# KMO_IO_MV2_6.net
KiCad netlist of a schematic drawn in EAGLE
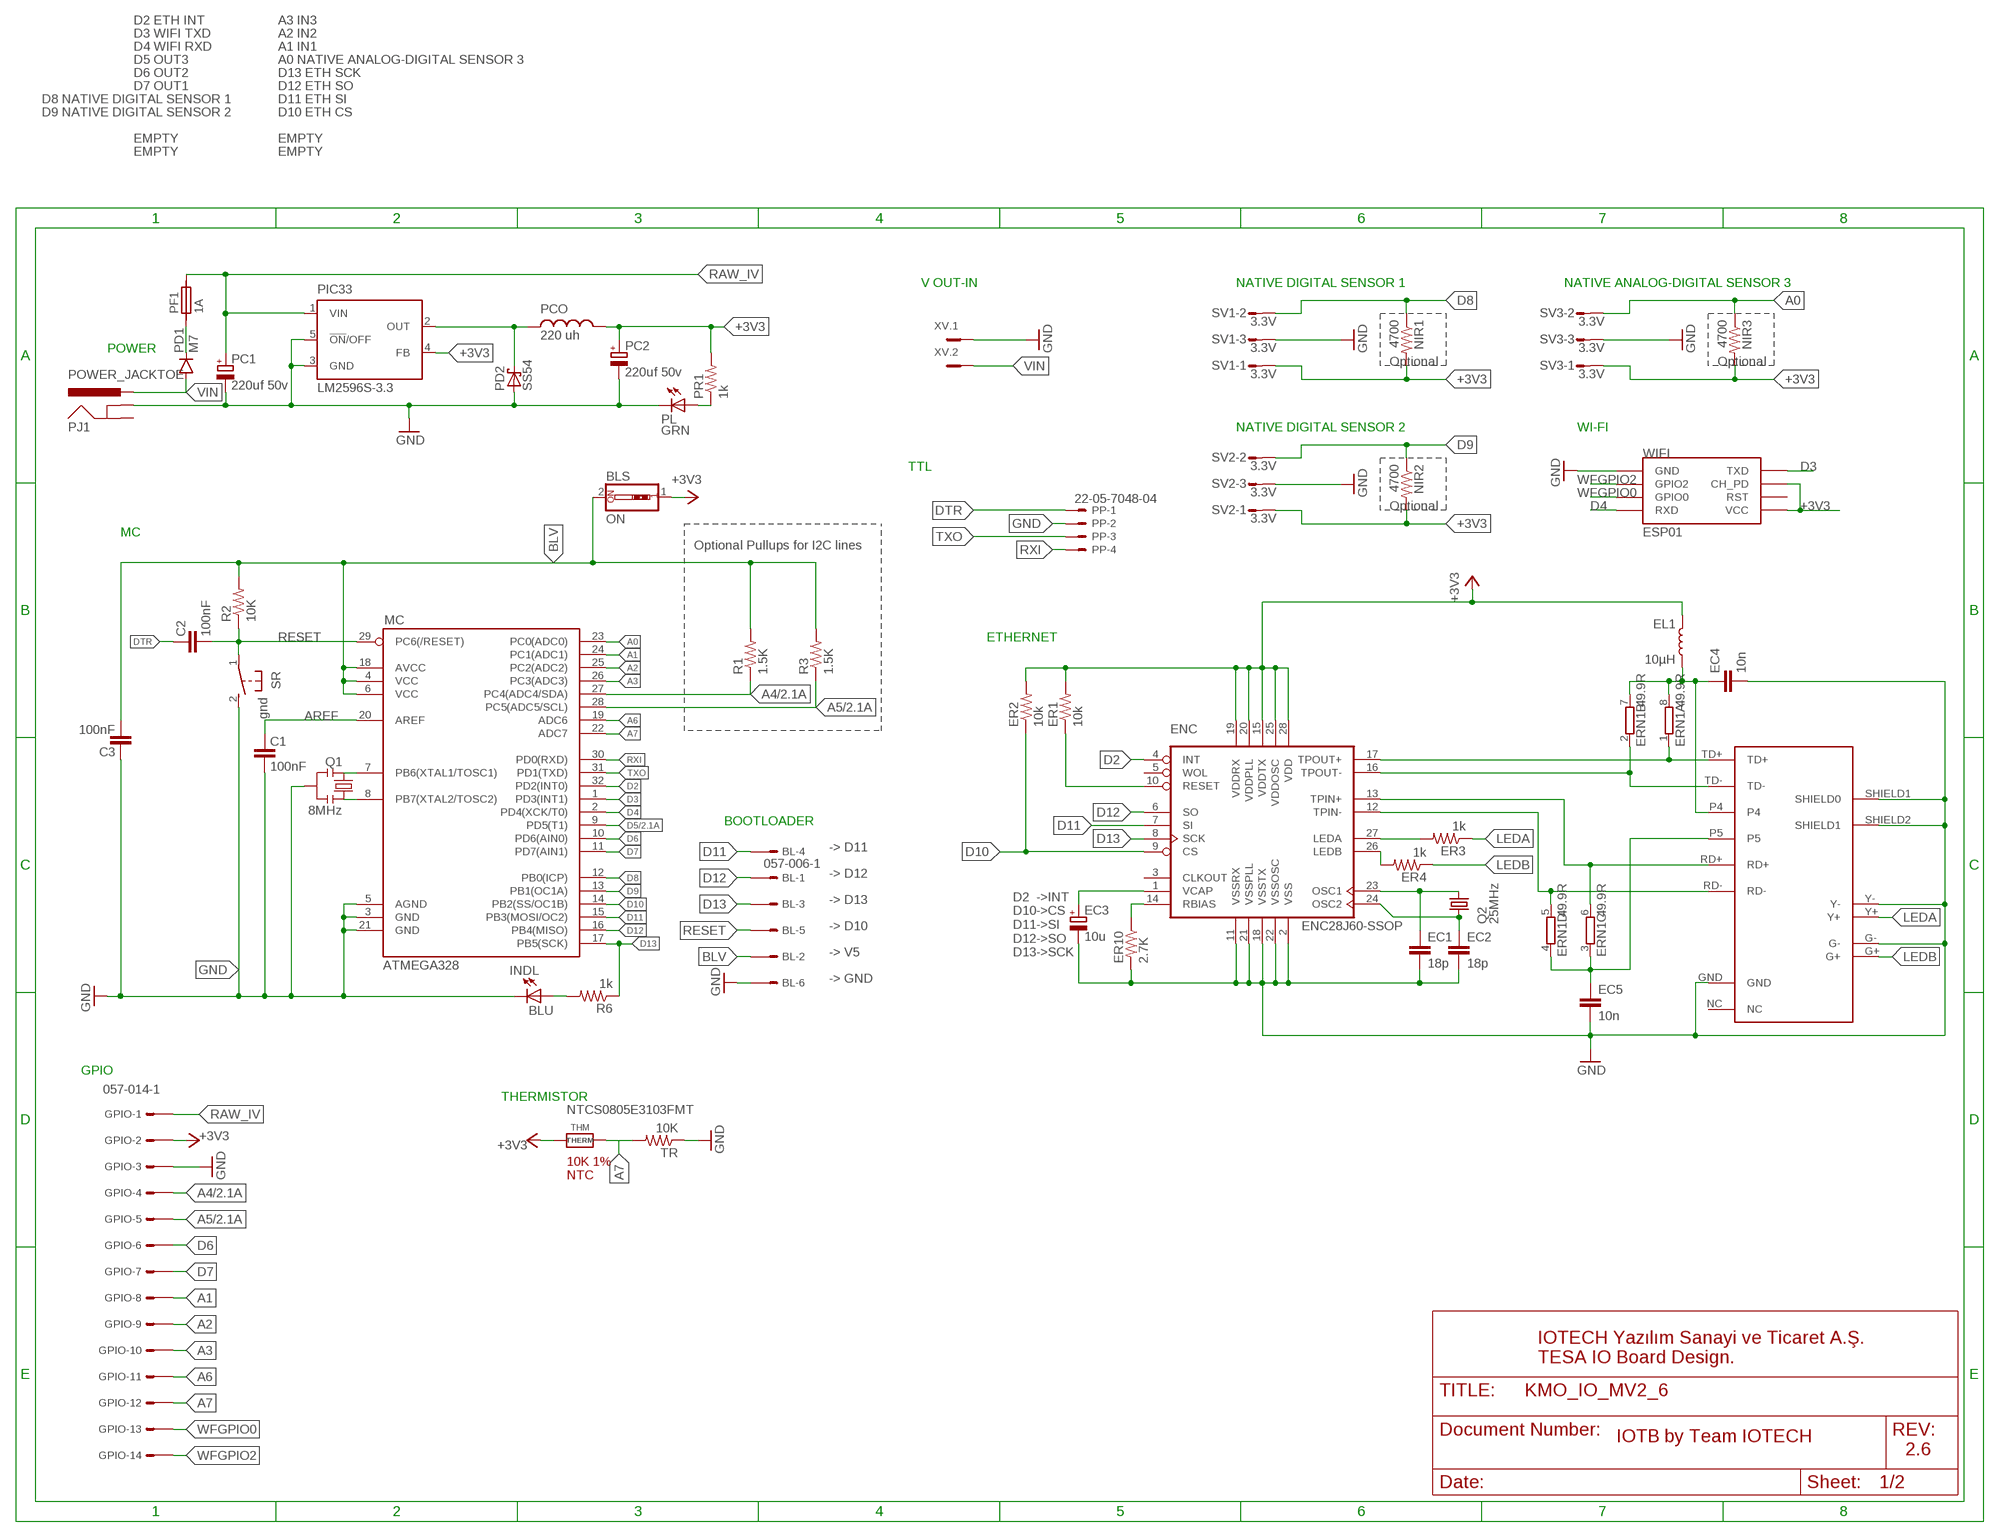
[diagram p0: schematic, sheet 1]
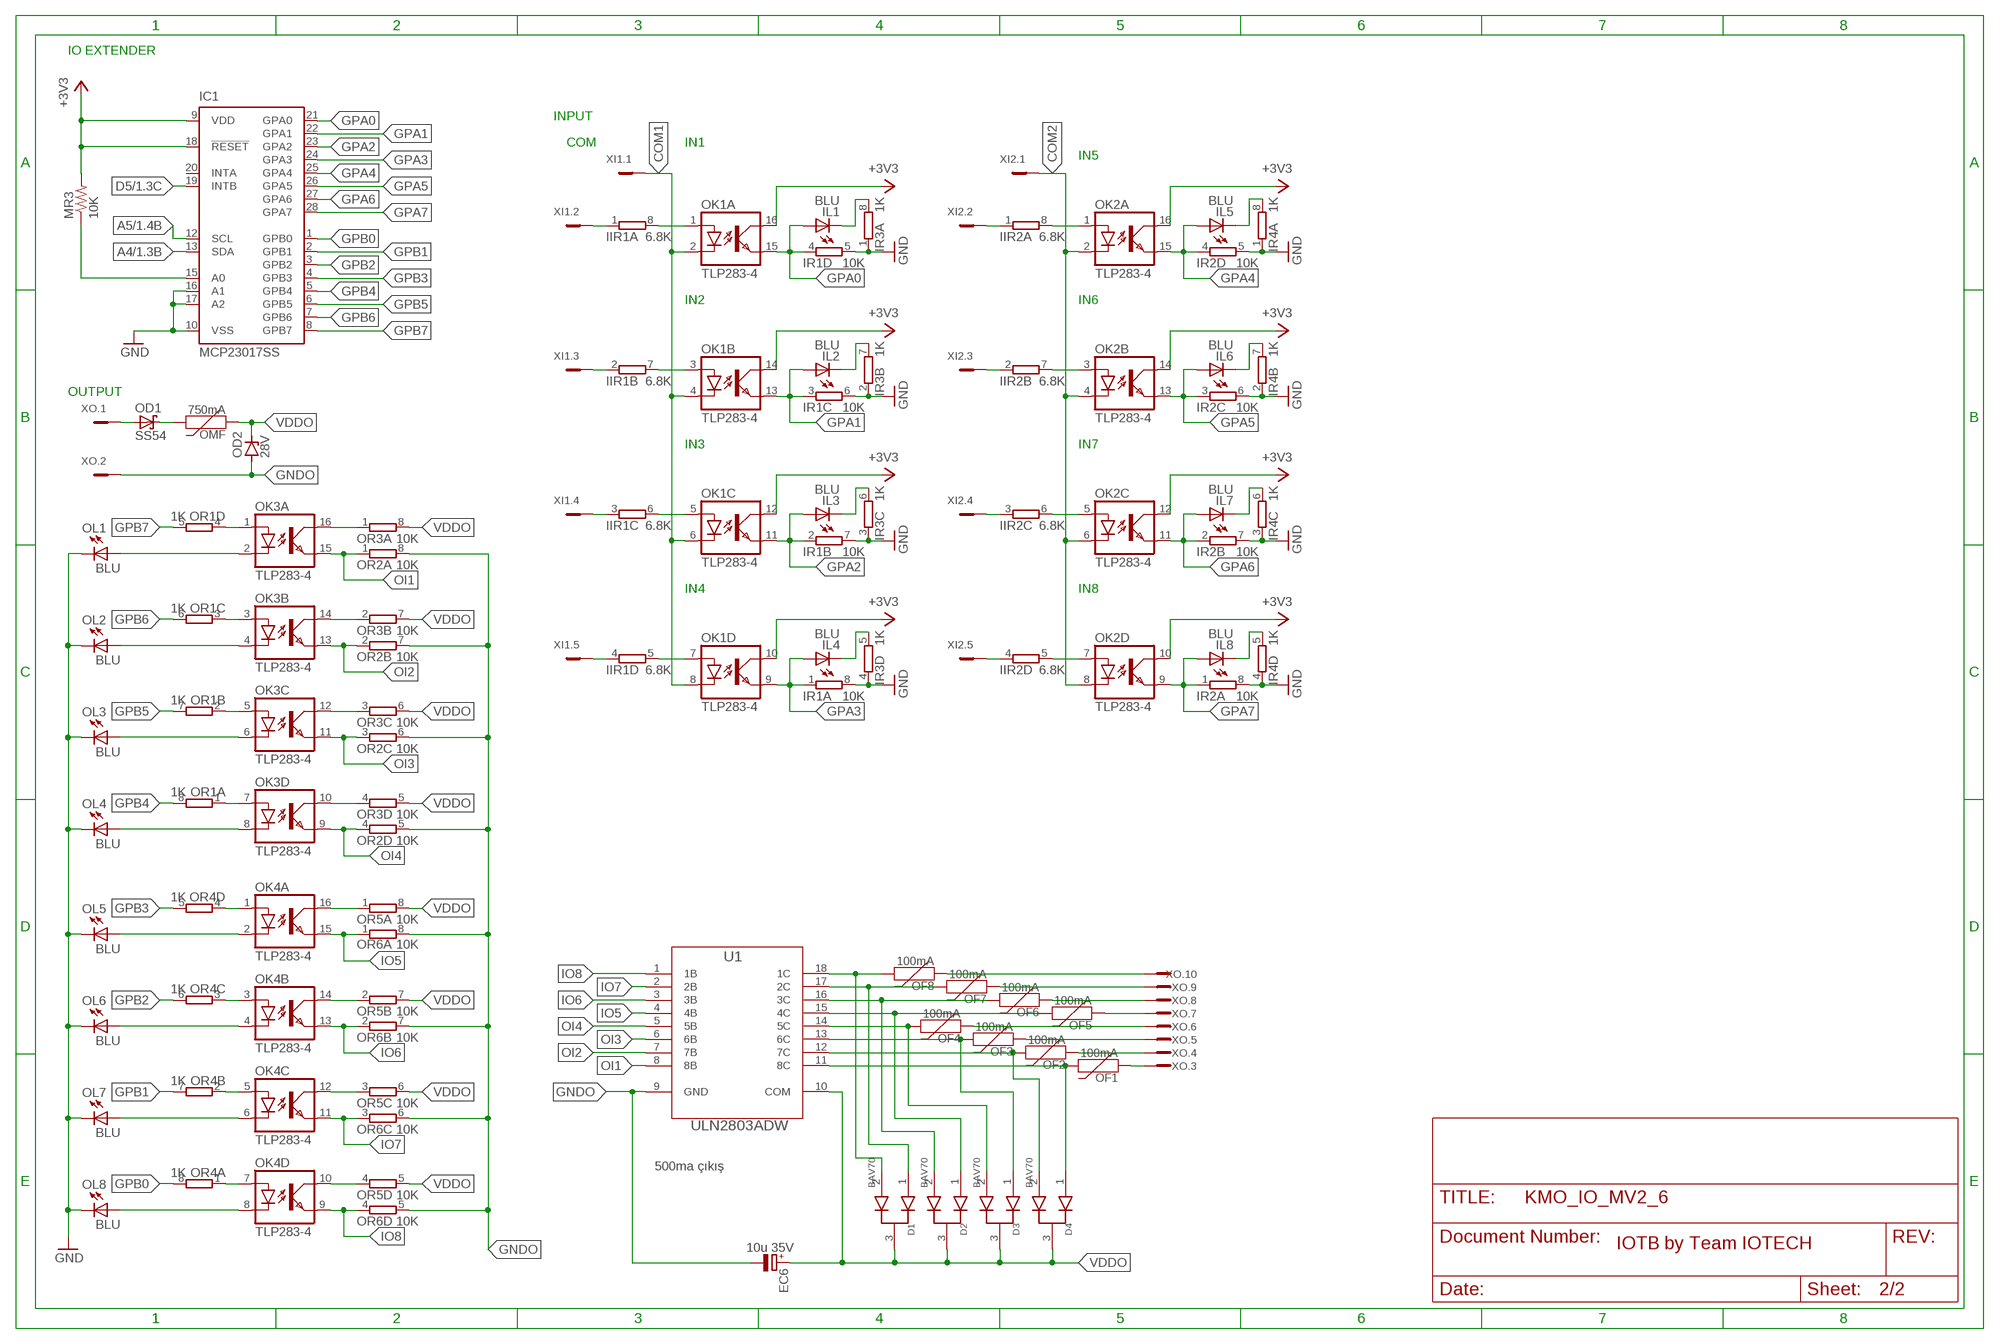
[diagram p1: schematic, sheet 2]

(export (version "E")
  (design (tool "Eeschema 10.0.6"))
  (components
    (comp (ref "D1")
      (value "BAV70")
      (footprint "eagle-import:SOT-23-3")
      (fields (field (name "MF") "Multicomp") (field (name "MP") "BAV70+"))
      (libsource (lib "eagle-import") (part "BAV70"))
    )
    (comp (ref "D2")
      (value "BAV70")
      (footprint "eagle-import:SOT-23-3")
      (fields (field (name "MF") "Multicomp") (field (name "MP") "BAV70+"))
      (libsource (lib "eagle-import") (part "BAV70"))
    )
    (comp (ref "D3")
      (value "BAV70")
      (footprint "eagle-import:SOT-23-3")
      (fields (field (name "MF") "Multicomp") (field (name "MP") "BAV70+"))
      (libsource (lib "eagle-import") (part "BAV70"))
    )
    (comp (ref "D4")
      (value "BAV70")
      (footprint "eagle-import:SOT-23-3")
      (fields (field (name "MF") "Multicomp") (field (name "MP") "BAV70+"))
      (libsource (lib "eagle-import") (part "BAV70"))
    )
    (comp (ref "EC6")
      (value "10u 35V")
      (footprint "eagle-import:CT3216")
      (libsource (lib "eagle-import") (part "CPOL-EUCT3216"))
    )
    (comp (ref "IC1")
      (value "MCP23017SS")
      (footprint "eagle-import:SSOP28")
      (fields (field (name "MF") "MICROCHIP") (field (name "MPN") "MCP23017-E/SS"))
      (libsource (lib "eagle-import") (part "MCP23017SS"))
    )
    (comp (ref "IIR1")
      (value "6.8K")
      (footprint "eagle-import:0603-ARV")
      (libsource (lib "eagle-import") (part "4R-N0603-ARV"))
    )
    (comp (ref "IIR2")
      (value "6.8K")
      (footprint "eagle-import:0603-ARV")
      (libsource (lib "eagle-import") (part "4R-N0603-ARV"))
    )
    (comp (ref "IL1")
      (value "BLU")
      (footprint "eagle-import:CHIP-LED0805")
      (libsource (lib "eagle-import") (part "LEDCHIP-LED0805"))
    )
    (comp (ref "IL2")
      (value "BLU")
      (footprint "eagle-import:CHIP-LED0805")
      (libsource (lib "eagle-import") (part "LEDCHIP-LED0805"))
    )
    (comp (ref "IL3")
      (value "BLU")
      (footprint "eagle-import:CHIP-LED0805")
      (libsource (lib "eagle-import") (part "LEDCHIP-LED0805"))
    )
    (comp (ref "IL4")
      (value "BLU")
      (footprint "eagle-import:CHIP-LED0805")
      (libsource (lib "eagle-import") (part "LEDCHIP-LED0805"))
    )
    (comp (ref "IL5")
      (value "BLU")
      (footprint "eagle-import:CHIP-LED0805")
      (libsource (lib "eagle-import") (part "LEDCHIP-LED0805"))
    )
    (comp (ref "IL6")
      (value "BLU")
      (footprint "eagle-import:CHIP-LED0805")
      (libsource (lib "eagle-import") (part "LEDCHIP-LED0805"))
    )
    (comp (ref "IL7")
      (value "BLU")
      (footprint "eagle-import:CHIP-LED0805")
      (libsource (lib "eagle-import") (part "LEDCHIP-LED0805"))
    )
    (comp (ref "IL8")
      (value "BLU")
      (footprint "eagle-import:CHIP-LED0805")
      (libsource (lib "eagle-import") (part "LEDCHIP-LED0805"))
    )
    (comp (ref "IR1")
      (value "10K")
      (footprint "eagle-import:0603-ARV")
      (libsource (lib "eagle-import") (part "4R-N0603-ARV"))
    )
    (comp (ref "IR2")
      (value "10K")
      (footprint "eagle-import:0603-ARV")
      (libsource (lib "eagle-import") (part "4R-N0603-ARV"))
    )
    (comp (ref "IR3")
      (value "1K")
      (footprint "eagle-import:0603-ARV")
      (libsource (lib "eagle-import") (part "4R-N0603-ARV"))
    )
    (comp (ref "IR4")
      (value "1K")
      (footprint "eagle-import:0603-ARV")
      (libsource (lib "eagle-import") (part "4R-N0603-ARV"))
    )
    (comp (ref "MR3")
      (value "10K")
      (footprint "eagle-import:0805")
      (libsource (lib "eagle-import") (part "RESISTOR0805-RES"))
    )
    (comp (ref "OD1")
      (value "SS54")
      (footprint "eagle-import:SMB")
      (libsource (lib "eagle-import") (part "SCHOTTKY-DIODESMD"))
    )
    (comp (ref "OD2")
      (value "28V")
      (footprint "eagle-import:SMB")
      (libsource (lib "eagle-import") (part "ZENER-DIODESMB"))
    )
    (comp (ref "OF1")
      (value "100mA")
      (footprint "eagle-import:1206")
      (libsource (lib "eagle-import") (part "PPTC_0.75A"))
    )
    (comp (ref "OF2")
      (value "100mA")
      (footprint "eagle-import:1206")
      (libsource (lib "eagle-import") (part "PPTC_0.75A"))
    )
    (comp (ref "OF3")
      (value "100mA")
      (footprint "eagle-import:1206")
      (libsource (lib "eagle-import") (part "PPTC_0.75A"))
    )
    (comp (ref "OF4")
      (value "100mA")
      (footprint "eagle-import:1206")
      (libsource (lib "eagle-import") (part "PPTC_0.75A"))
    )
    (comp (ref "OF5")
      (value "100mA")
      (footprint "eagle-import:1206")
      (libsource (lib "eagle-import") (part "PPTC_0.75A"))
    )
    (comp (ref "OF6")
      (value "100mA")
      (footprint "eagle-import:1206")
      (libsource (lib "eagle-import") (part "PPTC_0.75A"))
    )
    (comp (ref "OF7")
      (value "100mA")
      (footprint "eagle-import:1206")
      (libsource (lib "eagle-import") (part "PPTC_0.75A"))
    )
    (comp (ref "OF8")
      (value "100mA")
      (footprint "eagle-import:1206")
      (libsource (lib "eagle-import") (part "PPTC_0.75A"))
    )
    (comp (ref "OK1")
      (value "TLP283-4")
      (footprint "eagle-import:MINI-FLAT-16")
      (fields (field (name "SPICEPREFIX") "O"))
      (libsource (lib "eagle-import") (part "TLP283-4"))
    )
    (comp (ref "OK2")
      (value "TLP283-4")
      (footprint "eagle-import:MINI-FLAT-16")
      (fields (field (name "SPICEPREFIX") "O"))
      (libsource (lib "eagle-import") (part "TLP283-4"))
    )
    (comp (ref "OK3")
      (value "TLP283-4")
      (footprint "eagle-import:MINI-FLAT-16")
      (libsource (lib "eagle-import") (part "TLP283-4"))
    )
    (comp (ref "OK4")
      (value "TLP283-4")
      (footprint "eagle-import:MINI-FLAT-16")
      (libsource (lib "eagle-import") (part "TLP283-4"))
    )
    (comp (ref "OL1")
      (value "BLU")
      (footprint "eagle-import:CHIP-LED0805")
      (libsource (lib "eagle-import") (part "LEDCHIP-LED0805"))
    )
    (comp (ref "OL2")
      (value "BLU")
      (footprint "eagle-import:CHIP-LED0805")
      (libsource (lib "eagle-import") (part "LEDCHIP-LED0805"))
    )
    (comp (ref "OL3")
      (value "BLU")
      (footprint "eagle-import:CHIP-LED0805")
      (libsource (lib "eagle-import") (part "LEDCHIP-LED0805"))
    )
    (comp (ref "OL4")
      (value "BLU")
      (footprint "eagle-import:CHIP-LED0805")
      (libsource (lib "eagle-import") (part "LEDCHIP-LED0805"))
    )
    (comp (ref "OL5")
      (value "BLU")
      (footprint "eagle-import:CHIP-LED0805")
      (libsource (lib "eagle-import") (part "LEDCHIP-LED0805"))
    )
    (comp (ref "OL6")
      (value "BLU")
      (footprint "eagle-import:CHIP-LED0805")
      (libsource (lib "eagle-import") (part "LEDCHIP-LED0805"))
    )
    (comp (ref "OL7")
      (value "BLU")
      (footprint "eagle-import:CHIP-LED0805")
      (libsource (lib "eagle-import") (part "LEDCHIP-LED0805"))
    )
    (comp (ref "OL8")
      (value "BLU")
      (footprint "eagle-import:CHIP-LED0805")
      (libsource (lib "eagle-import") (part "LEDCHIP-LED0805"))
    )
    (comp (ref "OMF")
      (value "750mA")
      (footprint "eagle-import:1206")
      (libsource (lib "eagle-import") (part "PPTC_0.75A"))
    )
    (comp (ref "OR1")
      (value "1K")
      (footprint "eagle-import:0603-ARV")
      (libsource (lib "eagle-import") (part "4R-N0603-ARV"))
    )
    (comp (ref "OR2")
      (value "10K")
      (footprint "eagle-import:0603-ARV")
      (libsource (lib "eagle-import") (part "4R-N0603-ARV"))
    )
    (comp (ref "OR3")
      (value "10K")
      (footprint "eagle-import:0603-ARV")
      (libsource (lib "eagle-import") (part "4R-N0603-ARV"))
    )
    (comp (ref "OR4")
      (value "1K")
      (footprint "eagle-import:0603-ARV")
      (libsource (lib "eagle-import") (part "4R-N0603-ARV"))
    )
    (comp (ref "OR5")
      (value "10K")
      (footprint "eagle-import:0603-ARV")
      (libsource (lib "eagle-import") (part "4R-N0603-ARV"))
    )
    (comp (ref "OR6")
      (value "10K")
      (footprint "eagle-import:0603-ARV")
      (libsource (lib "eagle-import") (part "4R-N0603-ARV"))
    )
    (comp (ref "U1")
      (value "ULN2803ADW")
      (footprint "eagle-import:SOIC127P1030X265-18N")
      (libsource (lib "eagle-import") (part "ULN2803ADW"))
    )
    (comp (ref "XI1")
      (value "MC5")
      (footprint "eagle-import:MC5")
      (libsource (lib "eagle-import") (part "MC5"))
    )
    (comp (ref "XI2")
      (value "MC5")
      (footprint "eagle-import:MC5")
      (libsource (lib "eagle-import") (part "MC5"))
    )
    (comp (ref "XO")
      (value "MC10")
      (footprint "eagle-import:MC10")
      (libsource (lib "eagle-import") (part "MC10"))
    )
    (comp (ref "BL")
      (value "057-006-1")
      (footprint "eagle-import:057-006-1")
      (libsource (lib "eagle-import") (part "057-006-1"))
    )
    (comp (ref "BLS")
      (value "ON")
      (footprint "eagle-import:EDG-01")
      (libsource (lib "eagle-import") (part "SW_DIP-1"))
    )
    (comp (ref "C1")
      (value "100nF")
      (footprint "eagle-import:0805")
      (libsource (lib "eagle-import") (part "CAP0805"))
    )
    (comp (ref "C2")
      (value "100nF")
      (footprint "eagle-import:0805")
      (libsource (lib "eagle-import") (part "CAP0805"))
    )
    (comp (ref "C3")
      (value "100nF")
      (footprint "eagle-import:0805")
      (libsource (lib "eagle-import") (part "CAP0805"))
    )
    (comp (ref "EC1")
      (value "18p")
      (footprint "eagle-import:0805")
      (libsource (lib "eagle-import") (part "CAP0805"))
    )
    (comp (ref "EC2")
      (value "18p")
      (footprint "eagle-import:0805")
      (libsource (lib "eagle-import") (part "CAP0805"))
    )
    (comp (ref "EC3")
      (value "10u")
      (footprint "eagle-import:CT3216")
      (libsource (lib "eagle-import") (part "CPOL-EUCT3216"))
    )
    (comp (ref "EC4")
      (value "10n")
      (footprint "eagle-import:0805")
      (libsource (lib "eagle-import") (part "CAP0805"))
    )
    (comp (ref "EC5")
      (value "10n")
      (footprint "eagle-import:0805")
      (libsource (lib "eagle-import") (part "CAP0805"))
    )
    (comp (ref "EL1")
      (value "10µH")
      (footprint "eagle-import:0805")
      (libsource (lib "eagle-import") (part "INDUCTOR-0805-3.3UH"))
    )
    (comp (ref "ENC")
      (value "ENC28J60-SSOP")
      (footprint "eagle-import:SSOP28")
      (libsource (lib "eagle-import") (part "ENC28J60-SSOP"))
    )
    (comp (ref "ER1")
      (value "10k")
      (footprint "eagle-import:0805")
      (libsource (lib "eagle-import") (part "RESISTOR0805-RES"))
    )
    (comp (ref "ER2")
      (value "10k")
      (footprint "eagle-import:0805")
      (libsource (lib "eagle-import") (part "RESISTOR0805-RES"))
    )
    (comp (ref "ER3")
      (value "1k")
      (footprint "eagle-import:0805")
      (libsource (lib "eagle-import") (part "RESISTOR0805-RES"))
    )
    (comp (ref "ER4")
      (value "1k")
      (footprint "eagle-import:0805")
      (libsource (lib "eagle-import") (part "RESISTOR0805-RES"))
    )
    (comp (ref "ER10")
      (value "2.7K")
      (footprint "eagle-import:0805")
      (libsource (lib "eagle-import") (part "RESISTOR0805-RES"))
    )
    (comp (ref "ERN1")
      (value "49.9R")
      (footprint "eagle-import:0603-ARV")
      (libsource (lib "eagle-import") (part "4R-N0603-ARV"))
    )
    (comp (ref "GPIO")
      (value "057-014-1")
      (footprint "eagle-import:057-014-1")
      (libsource (lib "eagle-import") (part "057-014-1"))
    )
    (comp (ref "INDL")
      (value "BLU")
      (footprint "eagle-import:CHIP-LED0805")
      (libsource (lib "eagle-import") (part "LEDCHIP-LED0805"))
    )
    (comp (ref "MC")
      (value "ATMEGA328")
      (footprint "eagle-import:TQFP32-08")
      (libsource (lib "eagle-import") (part "ATMEGA168"))
    )
    (comp (ref "NIR1")
      (value "4700")
      (footprint "eagle-import:0805")
      (libsource (lib "eagle-import") (part "RESISTOR0805-RES"))
    )
    (comp (ref "NIR2")
      (value "4700")
      (footprint "eagle-import:0805")
      (libsource (lib "eagle-import") (part "RESISTOR0805-RES"))
    )
    (comp (ref "NIR3")
      (value "4700")
      (footprint "eagle-import:0805")
      (libsource (lib "eagle-import") (part "RESISTOR0805-RES"))
    )
    (comp (ref "PC1")
      (value "220uf 50v")
      (footprint "eagle-import:140CLH-1010")
      (libsource (lib "eagle-import") (part "CPOL-EU140CLH-1010"))
    )
    (comp (ref "PC2")
      (value "220uf 50v")
      (footprint "eagle-import:140CLH-1010")
      (libsource (lib "eagle-import") (part "CPOL-EU140CLH-1010"))
    )
    (comp (ref "PCO")
      (value "220 uh")
      (footprint "eagle-import:MSS1260")
      (libsource (lib "eagle-import") (part "MSS1260"))
    )
    (comp (ref "PD1")
      (value "M7")
      (footprint "eagle-import:SMA-DIODE")
      (libsource (lib "eagle-import") (part "DIODESMA"))
    )
    (comp (ref "PD2")
      (value "SS54")
      (footprint "eagle-import:SMB")
      (libsource (lib "eagle-import") (part "SCHOTTKY-DIODESMD"))
    )
    (comp (ref "PF1")
      (value "1A")
      (footprint "eagle-import:1820")
      (libsource (lib "eagle-import") (part "SIBA194600"))
    )
    (comp (ref "PIC33")
      (value "LM2596S-3.3")
      (footprint "eagle-import:TO263-5")
      (fields
        (field (name "MF") "NATIONAL SEMICONDUCTOR")
        (field (name "MPN") "LM2596S-ADJ/NOPB")
        (field (name "SPICEPREFIX") "X")
      )
      (libsource (lib "eagle-import") (part "LM2596S"))
    )
    (comp (ref "PJ1")
      (value "POWER_JACKTOE")
      (footprint "eagle-import:POWER_JACK_SMD_OVERPASTE_TOE")
      (libsource (lib "eagle-import") (part "POWER_JACKTOE"))
    )
    (comp (ref "PL")
      (value "GRN")
      (footprint "eagle-import:CHIP-LED0805")
      (libsource (lib "eagle-import") (part "LEDCHIP-LED0805"))
    )
    (comp (ref "PP")
      (value "22-05-7048-04")
      (footprint "eagle-import:7395-04")
      (fields (field (name "MF") "MOLEX"))
      (libsource (lib "eagle-import") (part "22-?-0405-7048"))
    )
    (comp (ref "PR1")
      (value "1k")
      (footprint "eagle-import:0805")
      (libsource (lib "eagle-import") (part "RESISTOR0805-RES"))
    )
    (comp (ref "Q1")
      (value "8MHz")
      (footprint "eagle-import:RESONATOR-SMD-1_1")
      (libsource (lib "eagle-import") (part "RESONATOR1{colon}1"))
    )
    (comp (ref "Q2")
      (value "25MHz")
      (footprint "eagle-import:5.0X3.2_2")
      (libsource (lib "eagle-import") (part "KX-9B"))
    )
    (comp (ref "R1")
      (value "1.5K")
      (footprint "eagle-import:0805")
      (libsource (lib "eagle-import") (part "RESISTOR0805-RES"))
    )
    (comp (ref "R2")
      (value "10K")
      (footprint "eagle-import:0805")
      (libsource (lib "eagle-import") (part "RESISTOR0805-RES"))
    )
    (comp (ref "R3")
      (value "1.5K")
      (footprint "eagle-import:0805")
      (libsource (lib "eagle-import") (part "RESISTOR0805-RES"))
    )
    (comp (ref "R6")
      (value "1k")
      (footprint "eagle-import:0805")
      (libsource (lib "eagle-import") (part "RESISTOR0805-RES"))
    )
    (comp (ref "SR")
      (value "gnd")
      (footprint "eagle-import:B3F-31XX")
      (fields (field (name "MPN") "B3F-3100"))
      (libsource (lib "eagle-import") (part "31-XX"))
    )
    (comp (ref "SV1")
      (value "3.3V")
      (footprint "eagle-import:S03P")
      (libsource (lib "eagle-import") (part "S03P"))
    )
    (comp (ref "SV2")
      (value "3.3V")
      (footprint "eagle-import:S03P")
      (libsource (lib "eagle-import") (part "S03P"))
    )
    (comp (ref "SV3")
      (value "3.3V")
      (footprint "eagle-import:S03P")
      (libsource (lib "eagle-import") (part "S03P"))
    )
    (comp (ref "THM")
      (value "THERM")
      (footprint "eagle-import:MICROBUILDER_0805_NOTHERMALS")
      (libsource (lib "eagle-import") (part "MICROBUILDER_RESISTOR0805_NOTHERMALS"))
    )
    (comp (ref "TR")
      (value "10K")
      (footprint "eagle-import:0805")
      (libsource (lib "eagle-import") (part "RESISTOR0805-RES"))
    )
    (comp (ref "U$2")
      (value "HR911105A")
      (footprint "eagle-import:RJ45")
      (libsource (lib "eagle-import") (part "HR911105A"))
    )
    (comp (ref "WIFI")
      (value "ESP01")
      (footprint "eagle-import:ESP01")
      (libsource (lib "eagle-import") (part "ESP01"))
    )
    (comp (ref "XV")
      (value "MC2")
      (footprint "eagle-import:MC2")
      (libsource (lib "eagle-import") (part "MC2"))
    )
  )
  (nets
    (net (code "1") (name "+3V3") (class "Default")
      (node (ref "BLS") (pin "1") (pinfunction "1_1") (pintype "passive"))
      (node (ref "EL1") (pin "1") (pinfunction "1_1") (pintype "passive"))
      (node (ref "ENC") (pin "15") (pinfunction "VDDTX_15") (pintype "power_in"))
      (node (ref "ENC") (pin "19") (pinfunction "VDDRX_19") (pintype "power_in"))
      (node (ref "ENC") (pin "20") (pinfunction "VDDPLL_20") (pintype "power_in"))
      (node (ref "ENC") (pin "25") (pinfunction "VDDOSC_25") (pintype "power_in"))
      (node (ref "ENC") (pin "28") (pinfunction "VDD_28") (pintype "power_in"))
      (node (ref "ER1") (pin "2") (pinfunction "2_2") (pintype "passive"))
      (node (ref "ER2") (pin "2") (pinfunction "2_2") (pintype "passive"))
      (node (ref "GPIO") (pin "2") (pinfunction "S_2") (pintype "passive"))
      (node (ref "IC1") (pin "18") (pinfunction "~{RESET}_18") (pintype "input"))
      (node (ref "IC1") (pin "9") (pinfunction "VDD_9") (pintype "power_in"))
      (node (ref "MR3") (pin "2") (pinfunction "2_2") (pintype "passive"))
      (node (ref "NIR1") (pin "2") (pinfunction "2_2") (pintype "passive"))
      (node (ref "NIR2") (pin "2") (pinfunction "2_2") (pintype "passive"))
      (node (ref "NIR3") (pin "2") (pinfunction "2_2") (pintype "passive"))
      (node (ref "OK1") (pin "10") (pinfunction "COL_10") (pintype "passive"))
      (node (ref "OK1") (pin "12") (pinfunction "COL_12") (pintype "passive"))
      (node (ref "OK1") (pin "14") (pinfunction "COL_14") (pintype "passive"))
      (node (ref "OK1") (pin "16") (pinfunction "COL_16") (pintype "passive"))
      (node (ref "OK2") (pin "10") (pinfunction "COL_10") (pintype "passive"))
      (node (ref "OK2") (pin "12") (pinfunction "COL_12") (pintype "passive"))
      (node (ref "OK2") (pin "14") (pinfunction "COL_14") (pintype "passive"))
      (node (ref "OK2") (pin "16") (pinfunction "COL_16") (pintype "passive"))
      (node (ref "PC2") (pin "+") (pinfunction "+_+") (pintype "passive"))
      (node (ref "PCO") (pin "P$1") (pinfunction "P$1_P$1") (pintype "passive"))
      (node (ref "PIC33") (pin "4") (pinfunction "FB_4") (pintype "input"))
      (node (ref "PR1") (pin "2") (pinfunction "2_2") (pintype "passive"))
      (node (ref "SV1") (pin "1") (pinfunction "S_1") (pintype "passive"))
      (node (ref "SV2") (pin "1") (pinfunction "S_1") (pintype "passive"))
      (node (ref "SV3") (pin "1") (pinfunction "S_1") (pintype "passive"))
      (node (ref "THM") (pin "1") (pinfunction "1_1") (pintype "passive"))
      (node (ref "WIFI") (pin "CH_PD") (pinfunction "CH_PD_CH_PD") (pintype "bidirectional"))
      (node (ref "WIFI") (pin "VCC") (pinfunction "VCC_VCC") (pintype "bidirectional"))
    )
    (net (code "2") (name "A0") (class "Default")
      (node (ref "MC") (pin "23") (pinfunction "PC0(ADC0)_23") (pintype "bidirectional"))
      (node (ref "NIR3") (pin "1") (pinfunction "1_1") (pintype "passive"))
      (node (ref "SV3") (pin "2") (pinfunction "S_2") (pintype "passive"))
    )
    (net (code "3") (name "A1") (class "Default")
      (node (ref "GPIO") (pin "8") (pinfunction "S_8") (pintype "passive"))
      (node (ref "MC") (pin "24") (pinfunction "PC1(ADC1)_24") (pintype "bidirectional"))
    )
    (net (code "4") (name "A2") (class "Default")
      (node (ref "GPIO") (pin "9") (pinfunction "S_9") (pintype "passive"))
      (node (ref "MC") (pin "25") (pinfunction "PC2(ADC2)_25") (pintype "bidirectional"))
    )
    (net (code "5") (name "A3") (class "Default")
      (node (ref "GPIO") (pin "10") (pinfunction "S_10") (pintype "passive"))
      (node (ref "MC") (pin "26") (pinfunction "PC3(ADC3)_26") (pintype "bidirectional"))
    )
    (net (code "6") (name "A4") (class "Default")
      (node (ref "GPIO") (pin "4") (pinfunction "S_4") (pintype "passive"))
      (node (ref "IC1") (pin "13") (pinfunction "SDA_13") (pintype "bidirectional"))
      (node (ref "MC") (pin "27") (pinfunction "PC4(ADC4/SDA)_27") (pintype "bidirectional"))
      (node (ref "R1") (pin "1") (pinfunction "1_1") (pintype "passive"))
    )
    (net (code "7") (name "A5") (class "Default")
      (node (ref "GPIO") (pin "5") (pinfunction "S_5") (pintype "passive"))
      (node (ref "IC1") (pin "12") (pinfunction "SCL_12") (pintype "input"))
      (node (ref "MC") (pin "28") (pinfunction "PC5(ADC5/SCL)_28") (pintype "bidirectional"))
      (node (ref "R3") (pin "1") (pinfunction "1_1") (pintype "passive"))
    )
    (net (code "8") (name "A6") (class "Default")
      (node (ref "GPIO") (pin "11") (pinfunction "S_11") (pintype "passive"))
      (node (ref "MC") (pin "19") (pinfunction "ADC6_19") (pintype "bidirectional"))
    )
    (net (code "9") (name "A7") (class "Default")
      (node (ref "GPIO") (pin "12") (pinfunction "S_12") (pintype "passive"))
      (node (ref "MC") (pin "22") (pinfunction "ADC7_22") (pintype "bidirectional"))
      (node (ref "THM") (pin "2") (pinfunction "2_2") (pintype "passive"))
      (node (ref "TR") (pin "2") (pinfunction "2_2") (pintype "passive"))
    )
    (net (code "10") (name "AREF") (class "Default")
      (node (ref "C1") (pin "2") (pinfunction "2_2") (pintype "passive"))
      (node (ref "MC") (pin "20") (pinfunction "AREF_20") (pintype "bidirectional"))
    )
    (net (code "11") (name "BLV") (class "Default")
      (node (ref "BL") (pin "2") (pinfunction "S_2") (pintype "passive"))
      (node (ref "BLS") (pin "2") (pinfunction "2_2") (pintype "passive"))
      (node (ref "C3") (pin "1") (pinfunction "1_1") (pintype "passive"))
      (node (ref "MC") (pin "18") (pinfunction "AVCC_18") (pintype "bidirectional"))
      (node (ref "MC") (pin "4") (pinfunction "VCC_4") (pintype "bidirectional"))
      (node (ref "MC") (pin "6") (pinfunction "VCC_6") (pintype "bidirectional"))
      (node (ref "R1") (pin "2") (pinfunction "2_2") (pintype "passive"))
      (node (ref "R2") (pin "2") (pinfunction "2_2") (pintype "passive"))
      (node (ref "R3") (pin "2") (pinfunction "2_2") (pintype "passive"))
    )
    (net (code "12") (name "COM1") (class "Default")
      (node (ref "OK1") (pin "2") (pinfunction "C_2") (pintype "passive"))
      (node (ref "OK1") (pin "4") (pinfunction "C_4") (pintype "passive"))
      (node (ref "OK1") (pin "6") (pinfunction "C_6") (pintype "passive"))
      (node (ref "OK1") (pin "8") (pinfunction "C_8") (pintype "passive"))
      (node (ref "XI1") (pin "1") (pinfunction "SK_1") (pintype "passive"))
    )
    (net (code "13") (name "COM2") (class "Default")
      (node (ref "OK2") (pin "2") (pinfunction "C_2") (pintype "passive"))
      (node (ref "OK2") (pin "4") (pinfunction "C_4") (pintype "passive"))
      (node (ref "OK2") (pin "6") (pinfunction "C_6") (pintype "passive"))
      (node (ref "OK2") (pin "8") (pinfunction "C_8") (pintype "passive"))
      (node (ref "XI2") (pin "1") (pinfunction "SK_1") (pintype "passive"))
    )
    (net (code "14") (name "D2") (class "Default")
      (node (ref "ENC") (pin "4") (pinfunction "INT_4") (pintype "output"))
      (node (ref "MC") (pin "32") (pinfunction "PD2(INT0)_32") (pintype "bidirectional"))
    )
    (net (code "15") (name "D3") (class "Default")
      (node (ref "MC") (pin "1") (pinfunction "PD3(INT1)_1") (pintype "bidirectional"))
      (node (ref "WIFI") (pin "TX") (pinfunction "TXD_TX") (pintype "bidirectional"))
    )
    (net (code "16") (name "D4") (class "Default")
      (node (ref "MC") (pin "2") (pinfunction "PD4(XCK/T0)_2") (pintype "bidirectional"))
      (node (ref "WIFI") (pin "RX") (pinfunction "RXD_RX") (pintype "bidirectional"))
    )
    (net (code "17") (name "D5") (class "Default")
      (node (ref "IC1") (pin "19") (pinfunction "INTB_19") (pintype "output"))
      (node (ref "MC") (pin "9") (pinfunction "PD5(T1)_9") (pintype "bidirectional"))
    )
    (net (code "18") (name "D6") (class "Default")
      (node (ref "GPIO") (pin "6") (pinfunction "S_6") (pintype "passive"))
      (node (ref "MC") (pin "10") (pinfunction "PD6(AIN0)_10") (pintype "bidirectional"))
    )
    (net (code "19") (name "D7") (class "Default")
      (node (ref "GPIO") (pin "7") (pinfunction "S_7") (pintype "passive"))
      (node (ref "MC") (pin "11") (pinfunction "PD7(AIN1)_11") (pintype "bidirectional"))
    )
    (net (code "20") (name "D8") (class "Default")
      (node (ref "MC") (pin "12") (pinfunction "PB0(ICP)_12") (pintype "bidirectional"))
      (node (ref "NIR1") (pin "1") (pinfunction "1_1") (pintype "passive"))
      (node (ref "SV1") (pin "2") (pinfunction "S_2") (pintype "passive"))
    )
    (net (code "21") (name "D9") (class "Default")
      (node (ref "MC") (pin "13") (pinfunction "PB1(OC1A)_13") (pintype "bidirectional"))
      (node (ref "NIR2") (pin "1") (pinfunction "1_1") (pintype "passive"))
      (node (ref "SV2") (pin "2") (pinfunction "S_2") (pintype "passive"))
    )
    (net (code "22") (name "D10") (class "Default")
      (node (ref "ENC") (pin "9") (pinfunction "CS_9") (pintype "input"))
      (node (ref "ER2") (pin "1") (pinfunction "1_1") (pintype "passive"))
      (node (ref "MC") (pin "14") (pinfunction "PB2(SS/OC1B)_14") (pintype "bidirectional"))
    )
    (net (code "23") (name "D11") (class "Default")
      (node (ref "BL") (pin "4") (pinfunction "S_4") (pintype "passive"))
      (node (ref "ENC") (pin "7") (pinfunction "SI_7") (pintype "input"))
      (node (ref "MC") (pin "15") (pinfunction "PB3(MOSI/OC2)_15") (pintype "bidirectional"))
    )
    (net (code "24") (name "D12") (class "Default")
      (node (ref "BL") (pin "1") (pinfunction "S_1") (pintype "passive"))
      (node (ref "ENC") (pin "6") (pinfunction "SO_6") (pintype "output"))
      (node (ref "MC") (pin "16") (pinfunction "PB4(MISO)_16") (pintype "bidirectional"))
    )
    (net (code "25") (name "D13") (class "Default")
      (node (ref "BL") (pin "3") (pinfunction "S_3") (pintype "passive"))
      (node (ref "ENC") (pin "8") (pinfunction "SCK_8") (pintype "input"))
      (node (ref "MC") (pin "17") (pinfunction "PB5(SCK)_17") (pintype "bidirectional"))
      (node (ref "R6") (pin "1") (pinfunction "1_1") (pintype "passive"))
    )
    (net (code "26") (name "DTR") (class "Default")
      (node (ref "C2") (pin "2") (pinfunction "2_2") (pintype "passive"))
      (node (ref "PP") (pin "1") (pinfunction "S_1") (pintype "passive"))
    )
    (net (code "27") (name "GND") (class "Default")
      (node (ref "BL") (pin "6") (pinfunction "S_6") (pintype "passive"))
      (node (ref "C1") (pin "1") (pinfunction "1_1") (pintype "passive"))
      (node (ref "C3") (pin "2") (pinfunction "2_2") (pintype "passive"))
      (node (ref "EC1") (pin "2") (pinfunction "2_2") (pintype "passive"))
      (node (ref "EC2") (pin "2") (pinfunction "2_2") (pintype "passive"))
      (node (ref "EC3") (pin "-") (pinfunction "-_-") (pintype "passive"))
      (node (ref "EC4") (pin "2") (pinfunction "2_2") (pintype "passive"))
      (node (ref "EC5") (pin "2") (pinfunction "2_2") (pintype "passive"))
      (node (ref "ENC") (pin "11") (pinfunction "VSSRX_11") (pintype "power_in"))
      (node (ref "ENC") (pin "18") (pinfunction "VSSTX_18") (pintype "power_in"))
      (node (ref "ENC") (pin "2") (pinfunction "VSS_2") (pintype "power_in"))
      (node (ref "ENC") (pin "21") (pinfunction "VSSPLL_21") (pintype "power_in"))
      (node (ref "ENC") (pin "22") (pinfunction "VSSOSC_22") (pintype "power_in"))
      (node (ref "ER10") (pin "2") (pinfunction "2_2") (pintype "passive"))
      (node (ref "GPIO") (pin "3") (pinfunction "S_3") (pintype "passive"))
      (node (ref "IC1") (pin "10") (pinfunction "VSS_10") (pintype "power_in"))
      (node (ref "IC1") (pin "16") (pinfunction "A1_16") (pintype "input"))
      (node (ref "IC1") (pin "17") (pinfunction "A2_17") (pintype "input"))
      (node (ref "INDL") (pin "C") (pinfunction "C_C") (pintype "passive"))
      (node (ref "IR1") (pin "5") (pinfunction "2_5") (pintype "passive"))
      (node (ref "IR1") (pin "6") (pinfunction "2_6") (pintype "passive"))
      (node (ref "IR1") (pin "7") (pinfunction "2_7") (pintype "passive"))
      (node (ref "IR1") (pin "8") (pinfunction "2_8") (pintype "passive"))
      (node (ref "IR2") (pin "5") (pinfunction "2_5") (pintype "passive"))
      (node (ref "IR2") (pin "6") (pinfunction "2_6") (pintype "passive"))
      (node (ref "IR2") (pin "7") (pinfunction "2_7") (pintype "passive"))
      (node (ref "IR2") (pin "8") (pinfunction "2_8") (pintype "passive"))
      (node (ref "IR3") (pin "1") (pinfunction "1_1") (pintype "passive"))
      (node (ref "IR3") (pin "2") (pinfunction "1_2") (pintype "passive"))
      (node (ref "IR3") (pin "3") (pinfunction "1_3") (pintype "passive"))
      (node (ref "IR3") (pin "4") (pinfunction "1_4") (pintype "passive"))
      (node (ref "IR4") (pin "1") (pinfunction "1_1") (pintype "passive"))
      (node (ref "IR4") (pin "2") (pinfunction "1_2") (pintype "passive"))
      (node (ref "IR4") (pin "3") (pinfunction "1_3") (pintype "passive"))
      (node (ref "IR4") (pin "4") (pinfunction "1_4") (pintype "passive"))
      (node (ref "MC") (pin "21") (pinfunction "GND_21") (pintype "bidirectional"))
      (node (ref "MC") (pin "3") (pinfunction "GND_3") (pintype "bidirectional"))
      (node (ref "MC") (pin "5") (pinfunction "AGND_5") (pintype "bidirectional"))
      (node (ref "OL1") (pin "C") (pinfunction "C_C") (pintype "passive"))
      (node (ref "OL2") (pin "C") (pinfunction "C_C") (pintype "passive"))
      (node (ref "OL3") (pin "C") (pinfunction "C_C") (pintype "passive"))
      (node (ref "OL4") (pin "C") (pinfunction "C_C") (pintype "passive"))
      (node (ref "OL5") (pin "C") (pinfunction "C_C") (pintype "passive"))
      (node (ref "OL6") (pin "C") (pinfunction "C_C") (pintype "passive"))
      (node (ref "OL7") (pin "C") (pinfunction "C_C") (pintype "passive"))
      (node (ref "OL8") (pin "C") (pinfunction "C_C") (pintype "passive"))
      (node (ref "PC1") (pin "-") (pinfunction "-_-") (pintype "passive"))
      (node (ref "PC2") (pin "-") (pinfunction "-_-") (pintype "passive"))
      (node (ref "PD2") (pin "A") (pinfunction "A_A") (pintype "passive"))
      (node (ref "PIC33") (pin "3") (pinfunction "GND_3") (pintype "power_in"))
      (node (ref "PIC33") (pin "5") (pinfunction "~{ON}/OFF_5") (pintype "input"))
      (node (ref "PJ1") (pin "GND") (pinfunction "GNDBREAK_GND") (pintype "bidirectional"))
      (node (ref "PL") (pin "C") (pinfunction "C_C") (pintype "passive"))
      (node (ref "PP") (pin "2") (pinfunction "S_2") (pintype "passive"))
      (node (ref "Q1") (pin "2") (pinfunction "2_2") (pintype "passive"))
      (node (ref "SR") (pin "2") (pinfunction "S_2") (pintype "passive"))
      (node (ref "SV1") (pin "3") (pinfunction "S_3") (pintype "passive"))
      (node (ref "SV2") (pin "3") (pinfunction "S_3") (pintype "passive"))
      (node (ref "SV3") (pin "3") (pinfunction "S_3") (pintype "passive"))
      (node (ref "TR") (pin "1") (pinfunction "1_1") (pintype "passive"))
      (node (ref "U$2") (pin "G-") (pinfunction "G-_G-") (pintype "bidirectional"))
      (node (ref "U$2") (pin "GND") (pinfunction "GND_GND") (pintype "bidirectional"))
      (node (ref "U$2") (pin "SHIELD1") (pinfunction "SHIELD0_SHIELD1") (pintype "bidirectional"))
      (node (ref "U$2") (pin "SHIELD2") (pinfunction "SHIELD1_SHIELD2") (pintype "bidirectional"))
      (node (ref "U$2") (pin "Y-") (pinfunction "Y-_Y-") (pintype "bidirectional"))
      (node (ref "WIFI") (pin "GND") (pinfunction "GND_GND") (pintype "bidirectional"))
      (node (ref "XV") (pin "1") (pinfunction "SK_1") (pintype "passive"))
    )
    (net (code "28") (name "GNDO") (class "Default")
      (node (ref "EC6") (pin "-") (pinfunction "-_-") (pintype "passive"))
      (node (ref "OD2") (pin "A") (pinfunction "A_A") (pintype "passive"))
      (node (ref "OR2") (pin "5") (pinfunction "2_5") (pintype "passive"))
      (node (ref "OR2") (pin "6") (pinfunction "2_6") (pintype "passive"))
      (node (ref "OR2") (pin "7") (pinfunction "2_7") (pintype "passive"))
      (node (ref "OR2") (pin "8") (pinfunction "2_8") (pintype "passive"))
      (node (ref "OR6") (pin "5") (pinfunction "2_5") (pintype "passive"))
      (node (ref "OR6") (pin "6") (pinfunction "2_6") (pintype "passive"))
      (node (ref "OR6") (pin "7") (pinfunction "2_7") (pintype "passive"))
      (node (ref "OR6") (pin "8") (pinfunction "2_8") (pintype "passive"))
      (node (ref "U1") (pin "9") (pinfunction "GND_9") (pintype "passive"))
      (node (ref "XO") (pin "2") (pinfunction "SK_2") (pintype "passive"))
    )
    (net (code "29") (name "GPA0") (class "Default")
      (node (ref "IC1") (pin "21") (pinfunction "GPA0_21") (pintype "bidirectional"))
      (node (ref "IL1") (pin "A") (pinfunction "A_A") (pintype "passive"))
      (node (ref "IR1") (pin "4") (pinfunction "1_4") (pintype "passive"))
      (node (ref "OK1") (pin "15") (pinfunction "EMIT_15") (pintype "passive"))
    )
    (net (code "30") (name "GPA1") (class "Default")
      (node (ref "IC1") (pin "22") (pinfunction "GPA1_22") (pintype "bidirectional"))
      (node (ref "IL2") (pin "A") (pinfunction "A_A") (pintype "passive"))
      (node (ref "IR1") (pin "3") (pinfunction "1_3") (pintype "passive"))
      (node (ref "OK1") (pin "13") (pinfunction "EMIT_13") (pintype "passive"))
    )
    (net (code "31") (name "GPA2") (class "Default")
      (node (ref "IC1") (pin "23") (pinfunction "GPA2_23") (pintype "bidirectional"))
      (node (ref "IL3") (pin "A") (pinfunction "A_A") (pintype "passive"))
      (node (ref "IR1") (pin "2") (pinfunction "1_2") (pintype "passive"))
      (node (ref "OK1") (pin "11") (pinfunction "EMIT_11") (pintype "passive"))
    )
    (net (code "32") (name "GPA3") (class "Default")
      (node (ref "IC1") (pin "24") (pinfunction "GPA3_24") (pintype "bidirectional"))
      (node (ref "IL4") (pin "A") (pinfunction "A_A") (pintype "passive"))
      (node (ref "IR1") (pin "1") (pinfunction "1_1") (pintype "passive"))
      (node (ref "OK1") (pin "9") (pinfunction "EMIT_9") (pintype "passive"))
    )
    (net (code "33") (name "GPA4") (class "Default")
      (node (ref "IC1") (pin "25") (pinfunction "GPA4_25") (pintype "bidirectional"))
      (node (ref "IL5") (pin "A") (pinfunction "A_A") (pintype "passive"))
      (node (ref "IR2") (pin "4") (pinfunction "1_4") (pintype "passive"))
      (node (ref "OK2") (pin "15") (pinfunction "EMIT_15") (pintype "passive"))
    )
    (net (code "34") (name "GPA5") (class "Default")
      (node (ref "IC1") (pin "26") (pinfunction "GPA5_26") (pintype "bidirectional"))
      (node (ref "IL6") (pin "A") (pinfunction "A_A") (pintype "passive"))
      (node (ref "IR2") (pin "3") (pinfunction "1_3") (pintype "passive"))
      (node (ref "OK2") (pin "13") (pinfunction "EMIT_13") (pintype "passive"))
    )
    (net (code "35") (name "GPA6") (class "Default")
      (node (ref "IC1") (pin "27") (pinfunction "GPA6_27") (pintype "bidirectional"))
      (node (ref "IL7") (pin "A") (pinfunction "A_A") (pintype "passive"))
      (node (ref "IR2") (pin "2") (pinfunction "1_2") (pintype "passive"))
      (node (ref "OK2") (pin "11") (pinfunction "EMIT_11") (pintype "passive"))
    )
    (net (code "36") (name "GPA7") (class "Default")
      (node (ref "IC1") (pin "28") (pinfunction "GPA7_28") (pintype "bidirectional"))
      (node (ref "IL8") (pin "A") (pinfunction "A_A") (pintype "passive"))
      (node (ref "IR2") (pin "1") (pinfunction "1_1") (pintype "passive"))
      (node (ref "OK2") (pin "9") (pinfunction "EMIT_9") (pintype "passive"))
    )
    (net (code "37") (name "GPB0") (class "Default")
      (node (ref "IC1") (pin "1") (pinfunction "GPB0_1") (pintype "bidirectional"))
      (node (ref "OR4") (pin "8") (pinfunction "2_8") (pintype "passive"))
    )
    (net (code "38") (name "GPB1") (class "Default")
      (node (ref "IC1") (pin "2") (pinfunction "GPB1_2") (pintype "bidirectional"))
      (node (ref "OR4") (pin "7") (pinfunction "2_7") (pintype "passive"))
    )
    (net (code "39") (name "GPB2") (class "Default")
      (node (ref "IC1") (pin "3") (pinfunction "GPB2_3") (pintype "bidirectional"))
      (node (ref "OR4") (pin "6") (pinfunction "2_6") (pintype "passive"))
    )
    (net (code "40") (name "GPB3") (class "Default")
      (node (ref "IC1") (pin "4") (pinfunction "GPB3_4") (pintype "bidirectional"))
      (node (ref "OR4") (pin "5") (pinfunction "2_5") (pintype "passive"))
    )
    (net (code "41") (name "GPB4") (class "Default")
      (node (ref "IC1") (pin "5") (pinfunction "GPB4_5") (pintype "bidirectional"))
      (node (ref "OR1") (pin "8") (pinfunction "2_8") (pintype "passive"))
    )
    (net (code "42") (name "GPB5") (class "Default")
      (node (ref "IC1") (pin "6") (pinfunction "GPB5_6") (pintype "bidirectional"))
      (node (ref "OR1") (pin "7") (pinfunction "2_7") (pintype "passive"))
    )
    (net (code "43") (name "GPB6") (class "Default")
      (node (ref "IC1") (pin "7") (pinfunction "GPB6_7") (pintype "bidirectional"))
      (node (ref "OR1") (pin "6") (pinfunction "2_6") (pintype "passive"))
    )
    (net (code "44") (name "GPB7") (class "Default")
      (node (ref "IC1") (pin "8") (pinfunction "GPB7_8") (pintype "bidirectional"))
      (node (ref "OR1") (pin "5") (pinfunction "2_5") (pintype "passive"))
    )
    (net (code "45") (name "IO5") (class "Default")
      (node (ref "OK4") (pin "15") (pinfunction "EMIT_15") (pintype "passive"))
      (node (ref "OR6") (pin "1") (pinfunction "1_1") (pintype "passive"))
      (node (ref "U1") (pin "4") (pinfunction "4B_4") (pintype "input"))
    )
    (net (code "46") (name "IO6") (class "Default")
      (node (ref "OK4") (pin "13") (pinfunction "EMIT_13") (pintype "passive"))
      (node (ref "OR6") (pin "2") (pinfunction "1_2") (pintype "passive"))
      (node (ref "U1") (pin "3") (pinfunction "3B_3") (pintype "input"))
    )
    (net (code "47") (name "IO7") (class "Default")
      (node (ref "OK4") (pin "11") (pinfunction "EMIT_11") (pintype "passive"))
      (node (ref "OR6") (pin "3") (pinfunction "1_3") (pintype "passive"))
      (node (ref "U1") (pin "2") (pinfunction "2B_2") (pintype "input"))
    )
    (net (code "48") (name "IO8") (class "Default")
      (node (ref "OK4") (pin "9") (pinfunction "EMIT_9") (pintype "passive"))
      (node (ref "OR6") (pin "4") (pinfunction "1_4") (pintype "passive"))
      (node (ref "U1") (pin "1") (pinfunction "1B_1") (pintype "input"))
    )
    (net (code "49") (name "LEDA") (class "Default")
      (node (ref "ER3") (pin "1") (pinfunction "1_1") (pintype "passive"))
      (node (ref "U$2") (pin "Y+") (pinfunction "Y+_Y+") (pintype "bidirectional"))
    )
    (net (code "50") (name "LEDB") (class "Default")
      (node (ref "ER4") (pin "1") (pinfunction "1_1") (pintype "passive"))
      (node (ref "U$2") (pin "G+") (pinfunction "G+_G+") (pintype "bidirectional"))
    )
    (net (code "51") (name "Net-(ENC-LEDA)") (class "Default")
      (node (ref "ENC") (pin "27") (pinfunction "LEDA_27") (pintype "output"))
      (node (ref "ER3") (pin "2") (pinfunction "2_2") (pintype "passive"))
    )
    (net (code "52") (name "Net-(ENC-LEDB)") (class "Default")
      (node (ref "ENC") (pin "26") (pinfunction "LEDB_26") (pintype "output"))
      (node (ref "ER4") (pin "2") (pinfunction "2_2") (pintype "passive"))
    )
    (net (code "53") (name "Net-(ENC-OSC1)") (class "Default")
      (node (ref "EC1") (pin "1") (pinfunction "1_1") (pintype "passive"))
      (node (ref "ENC") (pin "23") (pinfunction "OSC1_23") (pintype "input"))
      (node (ref "Q2") (pin "2") (pinfunction "2_2") (pintype "passive"))
    )
    (net (code "54") (name "Net-(ENC-OSC2)") (class "Default")
      (node (ref "EC2") (pin "1") (pinfunction "1_1") (pintype "passive"))
      (node (ref "ENC") (pin "24") (pinfunction "OSC2_24") (pintype "output"))
      (node (ref "Q2") (pin "1") (pinfunction "1_1") (pintype "passive"))
    )
    (net (code "55") (name "Net-(ENC-RBIAS)") (class "Default")
      (node (ref "ENC") (pin "14") (pinfunction "RBIAS_14") (pintype "passive"))
      (node (ref "ER10") (pin "1") (pinfunction "1_1") (pintype "passive"))
    )
    (net (code "56") (name "Net-(ENC-RESET)") (class "Default")
      (node (ref "ENC") (pin "10") (pinfunction "RESET_10") (pintype "input"))
      (node (ref "ER1") (pin "1") (pinfunction "1_1") (pintype "passive"))
    )
    (net (code "57") (name "Net-(ENC-TPIN+)") (class "Default")
      (node (ref "ENC") (pin "13") (pinfunction "TPIN+_13") (pintype "input"))
      (node (ref "ERN1") (pin "6") (pinfunction "2_6") (pintype "passive"))
      (node (ref "U$2") (pin "RD+") (pinfunction "RD+_RD+") (pintype "bidirectional"))
    )
    (net (code "58") (name "Net-(ENC-TPIN-)") (class "Default")
      (node (ref "ENC") (pin "12") (pinfunction "TPIN-_12") (pintype "input"))
      (node (ref "ERN1") (pin "5") (pinfunction "2_5") (pintype "passive"))
      (node (ref "U$2") (pin "RD-") (pinfunction "RD-_RD-") (pintype "bidirectional"))
    )
    (net (code "59") (name "Net-(ENC-TPOUT+)") (class "Default")
      (node (ref "ENC") (pin "17") (pinfunction "TPOUT+_17") (pintype "output"))
      (node (ref "ERN1") (pin "1") (pinfunction "1_1") (pintype "passive"))
      (node (ref "U$2") (pin "TD+") (pinfunction "TD+_TD+") (pintype "bidirectional"))
    )
    (net (code "60") (name "Net-(ENC-TPOUT-)") (class "Default")
      (node (ref "ENC") (pin "16") (pinfunction "TPOUT-_16") (pintype "output"))
      (node (ref "ERN1") (pin "2") (pinfunction "1_2") (pintype "passive"))
      (node (ref "U$2") (pin "TD-") (pinfunction "TD-_TD-") (pintype "bidirectional"))
    )
    (net (code "61") (name "Net-(ENC-VCAP)") (class "Default")
      (node (ref "EC3") (pin "+") (pinfunction "+_+") (pintype "passive"))
      (node (ref "ENC") (pin "1") (pinfunction "VCAP_1") (pintype "power_in"))
    )
    (net (code "62") (name "Net-(ERN1A-2)") (class "Default")
      (node (ref "EC4") (pin "1") (pinfunction "1_1") (pintype "passive"))
      (node (ref "EL1") (pin "2") (pinfunction "2_2") (pintype "passive"))
      (node (ref "ERN1") (pin "7") (pinfunction "2_7") (pintype "passive"))
      (node (ref "ERN1") (pin "8") (pinfunction "2_8") (pintype "passive"))
      (node (ref "U$2") (pin "P4") (pinfunction "P4_P4") (pintype "bidirectional"))
    )
    (net (code "63") (name "Net-(ERN1C-1)") (class "Default")
      (node (ref "EC5") (pin "1") (pinfunction "1_1") (pintype "passive"))
      (node (ref "ERN1") (pin "3") (pinfunction "1_3") (pintype "passive"))
      (node (ref "ERN1") (pin "4") (pinfunction "1_4") (pintype "passive"))
      (node (ref "U$2") (pin "P5") (pinfunction "P5_P5") (pintype "bidirectional"))
    )
    (net (code "64") (name "Net-(IC1-A0)") (class "Default")
      (node (ref "IC1") (pin "15") (pinfunction "A0_15") (pintype "input"))
      (node (ref "MR3") (pin "1") (pinfunction "1_1") (pintype "passive"))
    )
    (net (code "65") (name "Net-(IIR1A-2)") (class "Default")
      (node (ref "IIR1") (pin "8") (pinfunction "2_8") (pintype "passive"))
      (node (ref "OK1") (pin "1") (pinfunction "A_1") (pintype "passive"))
    )
    (net (code "66") (name "Net-(IIR1B-1)") (class "Default")
      (node (ref "IIR1") (pin "2") (pinfunction "1_2") (pintype "passive"))
      (node (ref "XI1") (pin "3") (pinfunction "SK_3") (pintype "passive"))
    )
    (net (code "67") (name "Net-(IIR1B-2)") (class "Default")
      (node (ref "IIR1") (pin "7") (pinfunction "2_7") (pintype "passive"))
      (node (ref "OK1") (pin "3") (pinfunction "A_3") (pintype "passive"))
    )
    (net (code "68") (name "Net-(IIR1C-1)") (class "Default")
      (node (ref "IIR1") (pin "3") (pinfunction "1_3") (pintype "passive"))
      (node (ref "XI1") (pin "4") (pinfunction "SK_4") (pintype "passive"))
    )
    (net (code "69") (name "Net-(IIR1C-2)") (class "Default")
      (node (ref "IIR1") (pin "6") (pinfunction "2_6") (pintype "passive"))
      (node (ref "OK1") (pin "5") (pinfunction "A_5") (pintype "passive"))
    )
    (net (code "70") (name "Net-(IIR1D-1)") (class "Default")
      (node (ref "IIR1") (pin "4") (pinfunction "1_4") (pintype "passive"))
      (node (ref "XI1") (pin "5") (pinfunction "SK_5") (pintype "passive"))
    )
    (net (code "71") (name "Net-(IIR1D-2)") (class "Default")
      (node (ref "IIR1") (pin "5") (pinfunction "2_5") (pintype "passive"))
      (node (ref "OK1") (pin "7") (pinfunction "A_7") (pintype "passive"))
    )
    (net (code "72") (name "Net-(IIR2A-2)") (class "Default")
      (node (ref "IIR2") (pin "8") (pinfunction "2_8") (pintype "passive"))
      (node (ref "OK2") (pin "1") (pinfunction "A_1") (pintype "passive"))
    )
    (net (code "73") (name "Net-(IIR2B-1)") (class "Default")
      (node (ref "IIR2") (pin "2") (pinfunction "1_2") (pintype "passive"))
      (node (ref "XI2") (pin "3") (pinfunction "SK_3") (pintype "passive"))
    )
    (net (code "74") (name "Net-(IIR2B-2)") (class "Default")
      (node (ref "IIR2") (pin "7") (pinfunction "2_7") (pintype "passive"))
      (node (ref "OK2") (pin "3") (pinfunction "A_3") (pintype "passive"))
    )
    (net (code "75") (name "Net-(IIR2C-1)") (class "Default")
      (node (ref "IIR2") (pin "3") (pinfunction "1_3") (pintype "passive"))
      (node (ref "XI2") (pin "4") (pinfunction "SK_4") (pintype "passive"))
    )
    (net (code "76") (name "Net-(IIR2C-2)") (class "Default")
      (node (ref "IIR2") (pin "6") (pinfunction "2_6") (pintype "passive"))
      (node (ref "OK2") (pin "5") (pinfunction "A_5") (pintype "passive"))
    )
    (net (code "77") (name "Net-(IIR2D-1)") (class "Default")
      (node (ref "IIR2") (pin "4") (pinfunction "1_4") (pintype "passive"))
      (node (ref "XI2") (pin "5") (pinfunction "SK_5") (pintype "passive"))
    )
    (net (code "78") (name "Net-(IIR2D-2)") (class "Default")
      (node (ref "IIR2") (pin "5") (pinfunction "2_5") (pintype "passive"))
      (node (ref "OK2") (pin "7") (pinfunction "A_7") (pintype "passive"))
    )
    (net (code "79") (name "Net-(INDL-PadA)") (class "Default")
      (node (ref "INDL") (pin "A") (pinfunction "A_A") (pintype "passive"))
      (node (ref "R6") (pin "2") (pinfunction "2_2") (pintype "passive"))
    )
    (net (code "80") (name "Net-(IR3A-2)") (class "Default")
      (node (ref "IL1") (pin "C") (pinfunction "C_C") (pintype "passive"))
      (node (ref "IR3") (pin "8") (pinfunction "2_8") (pintype "passive"))
    )
    (net (code "81") (name "Net-(IR3B-2)") (class "Default")
      (node (ref "IL2") (pin "C") (pinfunction "C_C") (pintype "passive"))
      (node (ref "IR3") (pin "7") (pinfunction "2_7") (pintype "passive"))
    )
    (net (code "82") (name "Net-(IR3C-2)") (class "Default")
      (node (ref "IL3") (pin "C") (pinfunction "C_C") (pintype "passive"))
      (node (ref "IR3") (pin "6") (pinfunction "2_6") (pintype "passive"))
    )
    (net (code "83") (name "Net-(IR3D-2)") (class "Default")
      (node (ref "IL4") (pin "C") (pinfunction "C_C") (pintype "passive"))
      (node (ref "IR3") (pin "5") (pinfunction "2_5") (pintype "passive"))
    )
    (net (code "84") (name "Net-(IR4A-2)") (class "Default")
      (node (ref "IL5") (pin "C") (pinfunction "C_C") (pintype "passive"))
      (node (ref "IR4") (pin "8") (pinfunction "2_8") (pintype "passive"))
    )
    (net (code "85") (name "Net-(IR4B-2)") (class "Default")
      (node (ref "IL6") (pin "C") (pinfunction "C_C") (pintype "passive"))
      (node (ref "IR4") (pin "7") (pinfunction "2_7") (pintype "passive"))
    )
    (net (code "86") (name "Net-(IR4C-2)") (class "Default")
      (node (ref "IL7") (pin "C") (pinfunction "C_C") (pintype "passive"))
      (node (ref "IR4") (pin "6") (pinfunction "2_6") (pintype "passive"))
    )
    (net (code "87") (name "Net-(IR4D-2)") (class "Default")
      (node (ref "IL8") (pin "C") (pinfunction "C_C") (pintype "passive"))
      (node (ref "IR4") (pin "5") (pinfunction "2_5") (pintype "passive"))
    )
    (net (code "88") (name "Net-(MC-PB6(XTAL1{slash}TOSC1))") (class "Default")
      (node (ref "MC") (pin "7") (pinfunction "PB6(XTAL1/TOSC1)_7") (pintype "bidirectional"))
      (node (ref "Q1") (pin "1") (pinfunction "1_1") (pintype "passive"))
    )
    (net (code "89") (name "Net-(MC-PB7(XTAL2{slash}TOSC2))") (class "Default")
      (node (ref "MC") (pin "8") (pinfunction "PB7(XTAL2/TOSC2)_8") (pintype "bidirectional"))
      (node (ref "Q1") (pin "3") (pinfunction "3_3") (pintype "passive"))
    )
    (net (code "90") (name "Net-(OD1-PadC)") (class "Default")
      (node (ref "OD1") (pin "C") (pinfunction "C_C") (pintype "passive"))
      (node (ref "OMF") (pin "2") (pinfunction "2_2") (pintype "bidirectional"))
    )
    (net (code "91") (name "Net-(OK3A-A)") (class "Default")
      (node (ref "OK3") (pin "1") (pinfunction "A_1") (pintype "passive"))
      (node (ref "OR1") (pin "4") (pinfunction "1_4") (pintype "passive"))
    )
    (net (code "92") (name "Net-(OK3A-C)") (class "Default")
      (node (ref "OK3") (pin "2") (pinfunction "C_2") (pintype "passive"))
      (node (ref "OL1") (pin "A") (pinfunction "A_A") (pintype "passive"))
    )
    (net (code "93") (name "Net-(OK3A-COL)") (class "Default")
      (node (ref "OK3") (pin "16") (pinfunction "COL_16") (pintype "passive"))
      (node (ref "OR3") (pin "1") (pinfunction "1_1") (pintype "passive"))
    )
    (net (code "94") (name "Net-(OK3B-A)") (class "Default")
      (node (ref "OK3") (pin "3") (pinfunction "A_3") (pintype "passive"))
      (node (ref "OR1") (pin "3") (pinfunction "1_3") (pintype "passive"))
    )
    (net (code "95") (name "Net-(OK3B-C)") (class "Default")
      (node (ref "OK3") (pin "4") (pinfunction "C_4") (pintype "passive"))
      (node (ref "OL2") (pin "A") (pinfunction "A_A") (pintype "passive"))
    )
    (net (code "96") (name "Net-(OK3B-COL)") (class "Default")
      (node (ref "OK3") (pin "14") (pinfunction "COL_14") (pintype "passive"))
      (node (ref "OR3") (pin "2") (pinfunction "1_2") (pintype "passive"))
    )
    (net (code "97") (name "Net-(OK3C-A)") (class "Default")
      (node (ref "OK3") (pin "5") (pinfunction "A_5") (pintype "passive"))
      (node (ref "OR1") (pin "2") (pinfunction "1_2") (pintype "passive"))
    )
    (net (code "98") (name "Net-(OK3C-C)") (class "Default")
      (node (ref "OK3") (pin "6") (pinfunction "C_6") (pintype "passive"))
      (node (ref "OL3") (pin "A") (pinfunction "A_A") (pintype "passive"))
    )
    (net (code "99") (name "Net-(OK3C-COL)") (class "Default")
      (node (ref "OK3") (pin "12") (pinfunction "COL_12") (pintype "passive"))
      (node (ref "OR3") (pin "3") (pinfunction "1_3") (pintype "passive"))
    )
    (net (code "100") (name "Net-(OK3D-A)") (class "Default")
      (node (ref "OK3") (pin "7") (pinfunction "A_7") (pintype "passive"))
      (node (ref "OR1") (pin "1") (pinfunction "1_1") (pintype "passive"))
    )
    (net (code "101") (name "Net-(OK3D-C)") (class "Default")
      (node (ref "OK3") (pin "8") (pinfunction "C_8") (pintype "passive"))
      (node (ref "OL4") (pin "A") (pinfunction "A_A") (pintype "passive"))
    )
    (net (code "102") (name "Net-(OK3D-COL)") (class "Default")
      (node (ref "OK3") (pin "10") (pinfunction "COL_10") (pintype "passive"))
      (node (ref "OR3") (pin "4") (pinfunction "1_4") (pintype "passive"))
    )
    (net (code "103") (name "Net-(OK4A-A)") (class "Default")
      (node (ref "OK4") (pin "1") (pinfunction "A_1") (pintype "passive"))
      (node (ref "OR4") (pin "4") (pinfunction "1_4") (pintype "passive"))
    )
    (net (code "104") (name "Net-(OK4A-C)") (class "Default")
      (node (ref "OK4") (pin "2") (pinfunction "C_2") (pintype "passive"))
      (node (ref "OL5") (pin "A") (pinfunction "A_A") (pintype "passive"))
    )
    (net (code "105") (name "Net-(OK4A-COL)") (class "Default")
      (node (ref "OK4") (pin "16") (pinfunction "COL_16") (pintype "passive"))
      (node (ref "OR5") (pin "1") (pinfunction "1_1") (pintype "passive"))
    )
    (net (code "106") (name "Net-(OK4B-A)") (class "Default")
      (node (ref "OK4") (pin "3") (pinfunction "A_3") (pintype "passive"))
      (node (ref "OR4") (pin "3") (pinfunction "1_3") (pintype "passive"))
    )
    (net (code "107") (name "Net-(OK4B-C)") (class "Default")
      (node (ref "OK4") (pin "4") (pinfunction "C_4") (pintype "passive"))
      (node (ref "OL6") (pin "A") (pinfunction "A_A") (pintype "passive"))
    )
    (net (code "108") (name "Net-(OK4B-COL)") (class "Default")
      (node (ref "OK4") (pin "14") (pinfunction "COL_14") (pintype "passive"))
      (node (ref "OR5") (pin "2") (pinfunction "1_2") (pintype "passive"))
    )
    (net (code "109") (name "Net-(OK4C-A)") (class "Default")
      (node (ref "OK4") (pin "5") (pinfunction "A_5") (pintype "passive"))
      (node (ref "OR4") (pin "2") (pinfunction "1_2") (pintype "passive"))
    )
    (net (code "110") (name "Net-(OK4C-C)") (class "Default")
      (node (ref "OK4") (pin "6") (pinfunction "C_6") (pintype "passive"))
      (node (ref "OL7") (pin "A") (pinfunction "A_A") (pintype "passive"))
    )
    (net (code "111") (name "Net-(OK4C-COL)") (class "Default")
      (node (ref "OK4") (pin "12") (pinfunction "COL_12") (pintype "passive"))
      (node (ref "OR5") (pin "3") (pinfunction "1_3") (pintype "passive"))
    )
    (net (code "112") (name "Net-(OK4D-A)") (class "Default")
      (node (ref "OK4") (pin "7") (pinfunction "A_7") (pintype "passive"))
      (node (ref "OR4") (pin "1") (pinfunction "1_1") (pintype "passive"))
    )
    (net (code "113") (name "Net-(OK4D-C)") (class "Default")
      (node (ref "OK4") (pin "8") (pinfunction "C_8") (pintype "passive"))
      (node (ref "OL8") (pin "A") (pinfunction "A_A") (pintype "passive"))
    )
    (net (code "114") (name "Net-(OK4D-COL)") (class "Default")
      (node (ref "OK4") (pin "10") (pinfunction "COL_10") (pintype "passive"))
      (node (ref "OR5") (pin "4") (pinfunction "1_4") (pintype "passive"))
    )
    (net (code "115") (name "Net-(PD1-PadC)") (class "Default")
      (node (ref "PD1") (pin "C") (pinfunction "C_C") (pintype "passive"))
      (node (ref "PF1") (pin "1") (pinfunction "1_1") (pintype "passive"))
    )
    (net (code "116") (name "Net-(PIC33-OUT)") (class "Default")
      (node (ref "PCO") (pin "P$2") (pinfunction "P$2_P$2") (pintype "passive"))
      (node (ref "PD2") (pin "C") (pinfunction "C_C") (pintype "passive"))
      (node (ref "PIC33") (pin "2") (pinfunction "OUT_2") (pintype "output"))
    )
    (net (code "117") (name "Net-(PL-PadA)") (class "Default")
      (node (ref "PL") (pin "A") (pinfunction "A_A") (pintype "passive"))
      (node (ref "PR1") (pin "1") (pinfunction "1_1") (pintype "passive"))
    )
    (net (code "118") (name "Net-(U1-1C)") (class "Default")
      (node (ref "D1") (pin "2") (pinfunction "2_2") (pintype "bidirectional"))
      (node (ref "OF8") (pin "2") (pinfunction "2_2") (pintype "bidirectional"))
      (node (ref "U1") (pin "18") (pinfunction "1C_18") (pintype "output"))
    )
    (net (code "119") (name "Net-(U1-2C)") (class "Default")
      (node (ref "D1") (pin "1") (pinfunction "1_1") (pintype "bidirectional"))
      (node (ref "OF7") (pin "2") (pinfunction "2_2") (pintype "bidirectional"))
      (node (ref "U1") (pin "17") (pinfunction "2C_17") (pintype "output"))
    )
    (net (code "120") (name "Net-(U1-3C)") (class "Default")
      (node (ref "D2") (pin "2") (pinfunction "2_2") (pintype "bidirectional"))
      (node (ref "OF6") (pin "2") (pinfunction "2_2") (pintype "bidirectional"))
      (node (ref "U1") (pin "16") (pinfunction "3C_16") (pintype "output"))
    )
    (net (code "121") (name "Net-(U1-4C)") (class "Default")
      (node (ref "D2") (pin "1") (pinfunction "1_1") (pintype "bidirectional"))
      (node (ref "OF5") (pin "2") (pinfunction "2_2") (pintype "bidirectional"))
      (node (ref "U1") (pin "15") (pinfunction "4C_15") (pintype "output"))
    )
    (net (code "122") (name "Net-(U1-5C)") (class "Default")
      (node (ref "D3") (pin "2") (pinfunction "2_2") (pintype "bidirectional"))
      (node (ref "OF4") (pin "2") (pinfunction "2_2") (pintype "bidirectional"))
      (node (ref "U1") (pin "14") (pinfunction "5C_14") (pintype "output"))
    )
    (net (code "123") (name "Net-(U1-6C)") (class "Default")
      (node (ref "D3") (pin "1") (pinfunction "1_1") (pintype "bidirectional"))
      (node (ref "OF3") (pin "2") (pinfunction "2_2") (pintype "bidirectional"))
      (node (ref "U1") (pin "13") (pinfunction "6C_13") (pintype "output"))
    )
    (net (code "124") (name "Net-(U1-7C)") (class "Default")
      (node (ref "D4") (pin "2") (pinfunction "2_2") (pintype "bidirectional"))
      (node (ref "OF2") (pin "2") (pinfunction "2_2") (pintype "bidirectional"))
      (node (ref "U1") (pin "12") (pinfunction "7C_12") (pintype "output"))
    )
    (net (code "125") (name "Net-(U1-8C)") (class "Default")
      (node (ref "D4") (pin "1") (pinfunction "1_1") (pintype "bidirectional"))
      (node (ref "OF1") (pin "2") (pinfunction "2_2") (pintype "bidirectional"))
      (node (ref "U1") (pin "11") (pinfunction "8C_11") (pintype "output"))
    )
    (net (code "126") (name "Net-(XI1B-SK)") (class "Default")
      (node (ref "IIR1") (pin "1") (pinfunction "1_1") (pintype "passive"))
      (node (ref "XI1") (pin "2") (pinfunction "SK_2") (pintype "passive"))
    )
    (net (code "127") (name "Net-(XI2B-SK)") (class "Default")
      (node (ref "IIR2") (pin "1") (pinfunction "1_1") (pintype "passive"))
      (node (ref "XI2") (pin "2") (pinfunction "SK_2") (pintype "passive"))
    )
    (net (code "128") (name "Net-(XOA-SK)") (class "Default")
      (node (ref "OD1") (pin "A") (pinfunction "A_A") (pintype "passive"))
      (node (ref "XO") (pin "1") (pinfunction "SK_1") (pintype "passive"))
    )
    (net (code "129") (name "Net-(XOB-SK)") (class "Default")
      (node (ref "OF8") (pin "1") (pinfunction "1_1") (pintype "bidirectional"))
      (node (ref "XO") (pin "10") (pinfunction "SK_10") (pintype "passive"))
    )
    (net (code "130") (name "Net-(XOD-SK)") (class "Default")
      (node (ref "OF1") (pin "1") (pinfunction "1_1") (pintype "bidirectional"))
      (node (ref "XO") (pin "3") (pinfunction "SK_3") (pintype "passive"))
    )
    (net (code "131") (name "Net-(XOE-SK)") (class "Default")
      (node (ref "OF2") (pin "1") (pinfunction "1_1") (pintype "bidirectional"))
      (node (ref "XO") (pin "4") (pinfunction "SK_4") (pintype "passive"))
    )
    (net (code "132") (name "Net-(XOF-SK)") (class "Default")
      (node (ref "OF3") (pin "1") (pinfunction "1_1") (pintype "bidirectional"))
      (node (ref "XO") (pin "5") (pinfunction "SK_5") (pintype "passive"))
    )
    (net (code "133") (name "Net-(XOG-SK)") (class "Default")
      (node (ref "OF4") (pin "1") (pinfunction "1_1") (pintype "bidirectional"))
      (node (ref "XO") (pin "6") (pinfunction "SK_6") (pintype "passive"))
    )
    (net (code "134") (name "Net-(XOH-SK)") (class "Default")
      (node (ref "OF5") (pin "1") (pinfunction "1_1") (pintype "bidirectional"))
      (node (ref "XO") (pin "7") (pinfunction "SK_7") (pintype "passive"))
    )
    (net (code "135") (name "Net-(XOI-SK)") (class "Default")
      (node (ref "OF6") (pin "1") (pinfunction "1_1") (pintype "bidirectional"))
      (node (ref "XO") (pin "8") (pinfunction "SK_8") (pintype "passive"))
    )
    (net (code "136") (name "Net-(XOJ-SK)") (class "Default")
      (node (ref "OF7") (pin "1") (pinfunction "1_1") (pintype "bidirectional"))
      (node (ref "XO") (pin "9") (pinfunction "SK_9") (pintype "passive"))
    )
    (net (code "137") (name "OI1") (class "Default")
      (node (ref "OK3") (pin "15") (pinfunction "EMIT_15") (pintype "passive"))
      (node (ref "OR2") (pin "1") (pinfunction "1_1") (pintype "passive"))
      (node (ref "U1") (pin "8") (pinfunction "8B_8") (pintype "input"))
    )
    (net (code "138") (name "OI2") (class "Default")
      (node (ref "OK3") (pin "13") (pinfunction "EMIT_13") (pintype "passive"))
      (node (ref "OR2") (pin "2") (pinfunction "1_2") (pintype "passive"))
      (node (ref "U1") (pin "7") (pinfunction "7B_7") (pintype "input"))
    )
    (net (code "139") (name "OI3") (class "Default")
      (node (ref "OK3") (pin "11") (pinfunction "EMIT_11") (pintype "passive"))
      (node (ref "OR2") (pin "3") (pinfunction "1_3") (pintype "passive"))
      (node (ref "U1") (pin "6") (pinfunction "6B_6") (pintype "input"))
    )
    (net (code "140") (name "OI4") (class "Default")
      (node (ref "OK3") (pin "9") (pinfunction "EMIT_9") (pintype "passive"))
      (node (ref "OR2") (pin "4") (pinfunction "1_4") (pintype "passive"))
      (node (ref "U1") (pin "5") (pinfunction "5B_5") (pintype "input"))
    )
    (net (code "141") (name "RAW_IV") (class "Default")
      (node (ref "GPIO") (pin "1") (pinfunction "S_1") (pintype "passive"))
      (node (ref "PC1") (pin "+") (pinfunction "+_+") (pintype "passive"))
      (node (ref "PF1") (pin "2") (pinfunction "2_2") (pintype "passive"))
      (node (ref "PIC33") (pin "1") (pinfunction "VIN_1") (pintype "input"))
    )
    (net (code "142") (name "RESET") (class "Default")
      (node (ref "BL") (pin "5") (pinfunction "S_5") (pintype "passive"))
      (node (ref "C2") (pin "1") (pinfunction "1_1") (pintype "passive"))
      (node (ref "MC") (pin "29") (pinfunction "PC6(/RESET)_29") (pintype "bidirectional"))
      (node (ref "R2") (pin "1") (pinfunction "1_1") (pintype "passive"))
      (node (ref "SR") (pin "1") (pinfunction "P_1") (pintype "passive"))
    )
    (net (code "143") (name "RXI") (class "Default")
      (node (ref "MC") (pin "30") (pinfunction "PD0(RXD)_30") (pintype "bidirectional"))
      (node (ref "PP") (pin "4") (pinfunction "S_4") (pintype "passive"))
    )
    (net (code "144") (name "TXO") (class "Default")
      (node (ref "MC") (pin "31") (pinfunction "PD1(TXD)_31") (pintype "bidirectional"))
      (node (ref "PP") (pin "3") (pinfunction "S_3") (pintype "passive"))
    )
    (net (code "145") (name "VDDO") (class "Default")
      (node (ref "D1") (pin "3") (pinfunction "3_3") (pintype "bidirectional"))
      (node (ref "D2") (pin "3") (pinfunction "3_3") (pintype "bidirectional"))
      (node (ref "D3") (pin "3") (pinfunction "3_3") (pintype "bidirectional"))
      (node (ref "D4") (pin "3") (pinfunction "3_3") (pintype "bidirectional"))
      (node (ref "EC6") (pin "+") (pinfunction "+_+") (pintype "passive"))
      (node (ref "OD2") (pin "C") (pinfunction "C_C") (pintype "passive"))
      (node (ref "OMF") (pin "1") (pinfunction "1_1") (pintype "bidirectional"))
      (node (ref "OR3") (pin "5") (pinfunction "2_5") (pintype "passive"))
      (node (ref "OR3") (pin "6") (pinfunction "2_6") (pintype "passive"))
      (node (ref "OR3") (pin "7") (pinfunction "2_7") (pintype "passive"))
      (node (ref "OR3") (pin "8") (pinfunction "2_8") (pintype "passive"))
      (node (ref "OR5") (pin "5") (pinfunction "2_5") (pintype "passive"))
      (node (ref "OR5") (pin "6") (pinfunction "2_6") (pintype "passive"))
      (node (ref "OR5") (pin "7") (pinfunction "2_7") (pintype "passive"))
      (node (ref "OR5") (pin "8") (pinfunction "2_8") (pintype "passive"))
      (node (ref "U1") (pin "10") (pinfunction "COM_10") (pintype "output"))
    )
    (net (code "146") (name "VIN") (class "Default")
      (node (ref "PD1") (pin "A") (pinfunction "A_A") (pintype "passive"))
      (node (ref "PJ1") (pin "VIN0") (pinfunction "PWR_VIN0") (pintype "bidirectional"))
      (node (ref "XV") (pin "2") (pinfunction "SK_2") (pintype "passive"))
    )
    (net (code "147") (name "WFGPIO0") (class "Default")
      (node (ref "GPIO") (pin "13") (pinfunction "S_13") (pintype "passive"))
      (node (ref "WIFI") (pin "GPIO0") (pinfunction "GPIO0_GPIO0") (pintype "bidirectional"))
    )
    (net (code "148") (name "WFGPIO2") (class "Default")
      (node (ref "GPIO") (pin "14") (pinfunction "S_14") (pintype "passive"))
      (node (ref "WIFI") (pin "GPIO2") (pinfunction "GPIO2_GPIO2") (pintype "bidirectional"))
    )
    (net (code "149") (name "unconnected-(ENC-CLKOUT-Pad3)") (class "Default")
      (node (ref "ENC") (pin "3") (pinfunction "CLKOUT_3") (pintype "output"))
    )
    (net (code "150") (name "unconnected-(ENC-WOL-Pad5)") (class "Default")
      (node (ref "ENC") (pin "5") (pinfunction "WOL_5") (pintype "output"))
    )
    (net (code "151") (name "unconnected-(IC1-INTA-Pad20)") (class "Default")
      (node (ref "IC1") (pin "20") (pinfunction "INTA_20") (pintype "output"))
    )
    (net (code "152") (name "unconnected-(PJ1-GND-PadP$4)") (class "Default")
      (node (ref "PJ1") (pin "P$4") (pinfunction "GND_P$4") (pintype "bidirectional"))
    )
    (net (code "153") (name "unconnected-(U$2-PadNC)") (class "Default")
      (node (ref "U$2") (pin "NC") (pinfunction "NC_NC") (pintype "bidirectional"))
    )
    (net (code "154") (name "unconnected-(WIFI-PadRST)") (class "Default")
      (node (ref "WIFI") (pin "RST") (pinfunction "RST_RST") (pintype "bidirectional"))
    )
  )
)
